# board.net
KiCad netlist of a schematic drawn in EAGLE
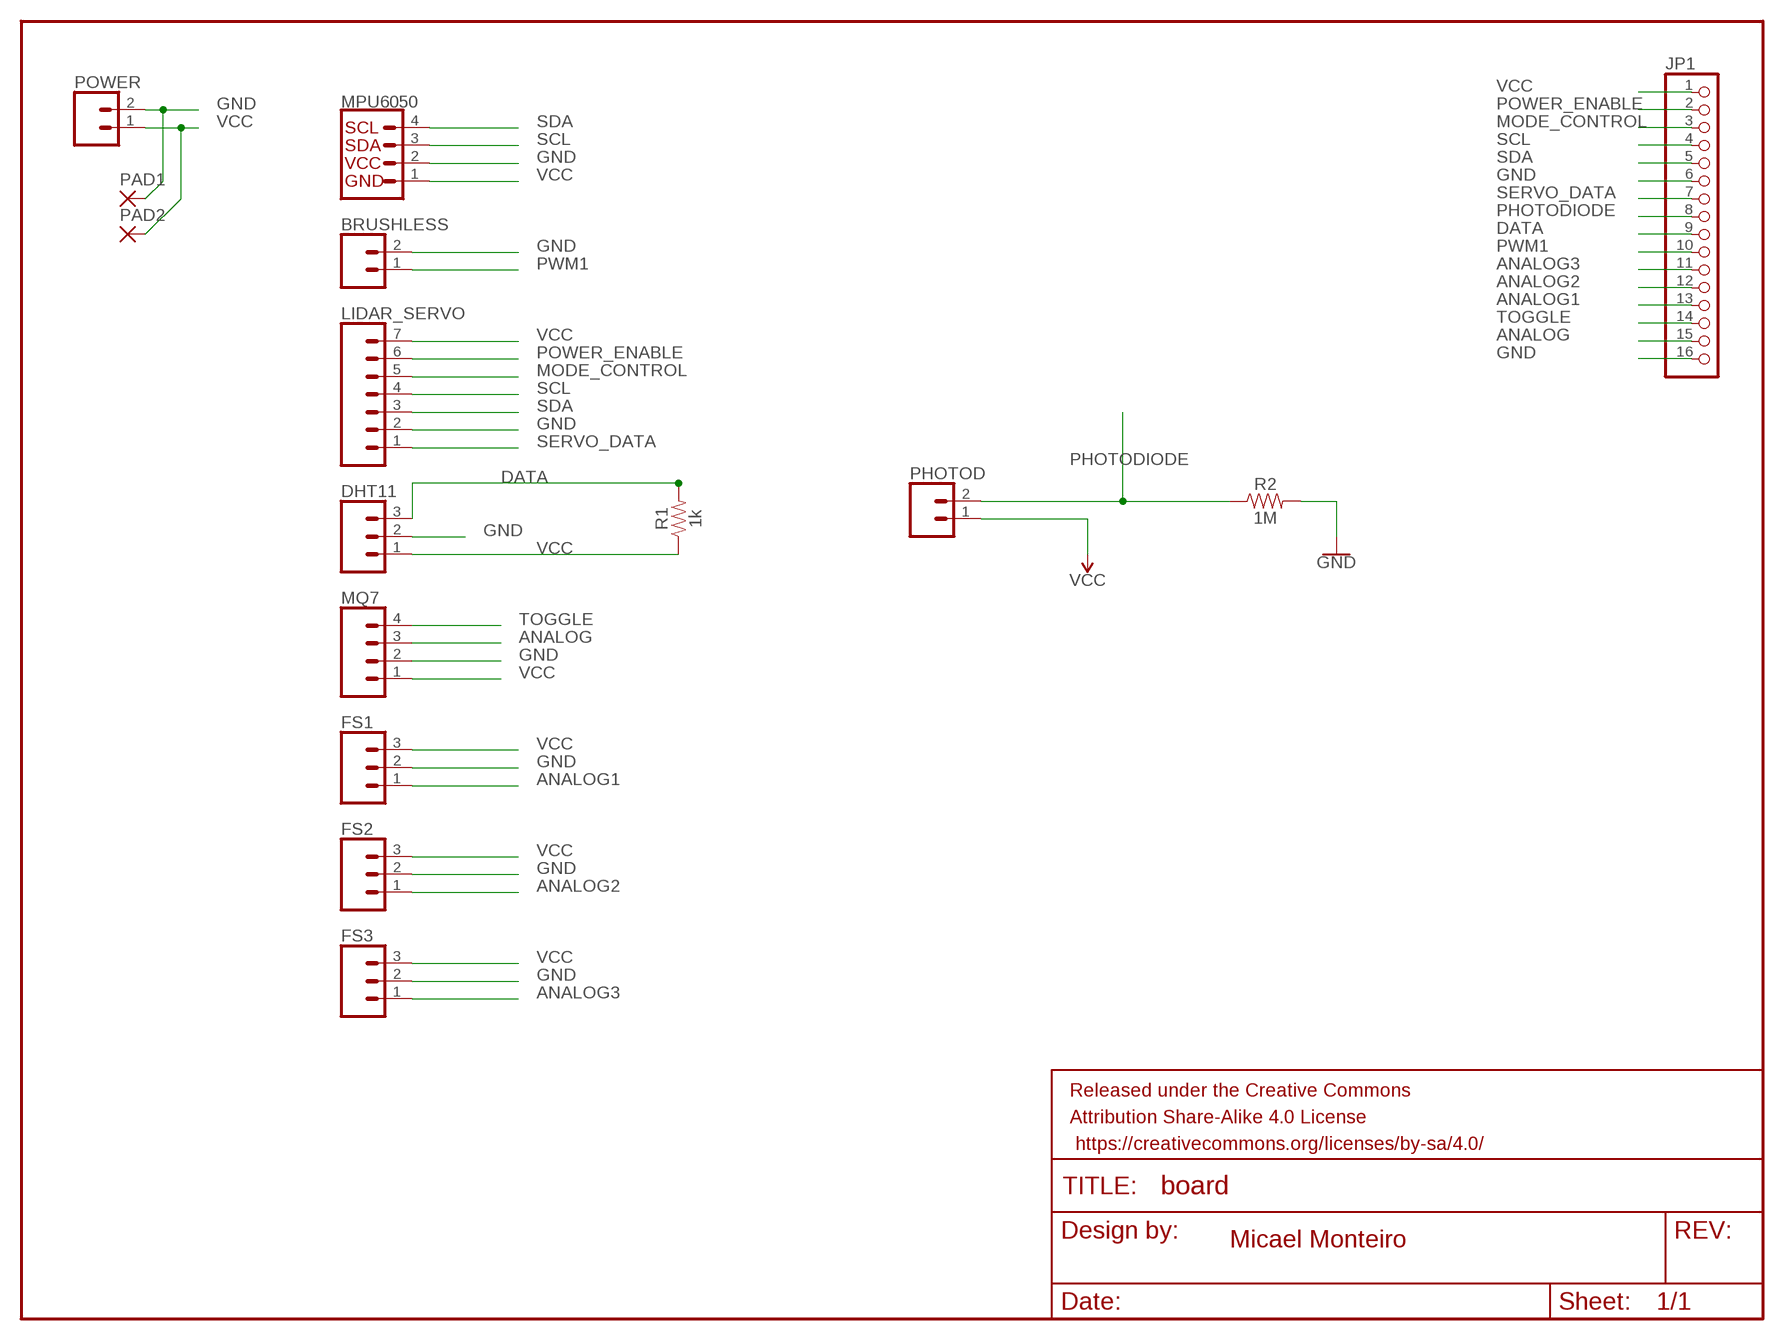
[diagram p0: schematic, sheet 1]

(export (version "E")
  (design (tool "Eeschema 10.0.6"))
  (components
    (comp (ref "BRUSHLESS")
      (value "CONN_02")
      (footprint "eagle-import:1X02")
      (libsource (lib "eagle-import") (part "CONN_02"))
    )
    (comp (ref "DHT11")
      (value "CONN_03")
      (footprint "eagle-import:1X03")
      (libsource (lib "eagle-import") (part "CONN_03"))
    )
    (comp (ref "FRAME1")
      (value "FRAME-LETTER")
      (footprint "eagle-import:CREATIVE_COMMONS")
      (libsource (lib "eagle-import") (part "FRAME-LETTER"))
    )
    (comp (ref "FS1")
      (value "CONN_03")
      (footprint "eagle-import:1X03")
      (libsource (lib "eagle-import") (part "CONN_03"))
    )
    (comp (ref "FS2")
      (value "CONN_03")
      (footprint "eagle-import:1X03")
      (libsource (lib "eagle-import") (part "CONN_03"))
    )
    (comp (ref "FS3")
      (value "CONN_03")
      (footprint "eagle-import:1X03")
      (libsource (lib "eagle-import") (part "CONN_03"))
    )
    (comp (ref "JP1")
      (value "PINHD-1X16")
      (footprint "eagle-import:1X16")
      (libsource (lib "eagle-import") (part "PINHD-1X16"))
    )
    (comp (ref "LIDAR_SERVO")
      (value "CONN_07")
      (footprint "eagle-import:1X07")
      (libsource (lib "eagle-import") (part "CONN_07"))
    )
    (comp (ref "MPU6050")
      (value "I2C_STANDARD")
      (footprint "eagle-import:1X04")
      (libsource (lib "eagle-import") (part "I2C_STANDARD"))
    )
    (comp (ref "MQ7")
      (value "CONN_04")
      (footprint "eagle-import:1X04")
      (libsource (lib "eagle-import") (part "CONN_04"))
    )
    (comp (ref "PAD1")
      (value "1,6/0,9")
      (footprint "eagle-import:1,6_0,9")
      (libsource (lib "eagle-import") (part "1,6/0,9"))
    )
    (comp (ref "PAD2")
      (value "1,6/0,9")
      (footprint "eagle-import:1,6_0,9")
      (libsource (lib "eagle-import") (part "1,6/0,9"))
    )
    (comp (ref "PHOTOD")
      (value "CONN_02")
      (footprint "eagle-import:1X02")
      (libsource (lib "eagle-import") (part "CONN_02"))
    )
    (comp (ref "POWER")
      (value "CONN_02")
      (footprint "eagle-import:1X02")
      (libsource (lib "eagle-import") (part "CONN_02"))
    )
    (comp (ref "R1")
      (value "1k")
      (footprint "eagle-import:0603")
      (libsource (lib "eagle-import") (part "1KOHM-0603-1/10W-1%"))
    )
    (comp (ref "R2")
      (value "1M")
      (footprint "eagle-import:0603")
      (libsource (lib "eagle-import") (part "1MOHM-0603-1/4W-5%"))
    )
  )
  (nets
    (net (code "1") (name "/ANALOG") (class "Default")
      (node (ref "JP1") (pin "15") (pinfunction "15_15") (pintype "passive"))
      (node (ref "MQ7") (pin "3") (pinfunction "3_3") (pintype "passive"))
    )
    (net (code "2") (name "/ANALOG1") (class "Default")
      (node (ref "FS1") (pin "1") (pinfunction "1_1") (pintype "passive"))
      (node (ref "JP1") (pin "13") (pinfunction "13_13") (pintype "passive"))
    )
    (net (code "3") (name "/ANALOG2") (class "Default")
      (node (ref "FS2") (pin "1") (pinfunction "1_1") (pintype "passive"))
      (node (ref "JP1") (pin "12") (pinfunction "12_12") (pintype "passive"))
    )
    (net (code "4") (name "/ANALOG3") (class "Default")
      (node (ref "FS3") (pin "1") (pinfunction "1_1") (pintype "passive"))
      (node (ref "JP1") (pin "11") (pinfunction "11_11") (pintype "passive"))
    )
    (net (code "5") (name "/DATA") (class "Default")
      (node (ref "DHT11") (pin "3") (pinfunction "3_3") (pintype "passive"))
      (node (ref "JP1") (pin "9") (pinfunction "9_9") (pintype "passive"))
      (node (ref "R1") (pin "2") (pinfunction "2_2") (pintype "passive"))
    )
    (net (code "6") (name "/MODE_CONTROL") (class "Default")
      (node (ref "JP1") (pin "3") (pinfunction "3_3") (pintype "passive"))
      (node (ref "LIDAR_SERVO") (pin "5") (pinfunction "5_5") (pintype "passive"))
    )
    (net (code "7") (name "/PHOTODIODE") (class "Default")
      (node (ref "JP1") (pin "8") (pinfunction "8_8") (pintype "passive"))
      (node (ref "PHOTOD") (pin "2") (pinfunction "2_2") (pintype "passive"))
      (node (ref "R2") (pin "1") (pinfunction "1_1") (pintype "passive"))
    )
    (net (code "8") (name "/POWER_ENABLE") (class "Default")
      (node (ref "JP1") (pin "2") (pinfunction "2_2") (pintype "passive"))
      (node (ref "LIDAR_SERVO") (pin "6") (pinfunction "6_6") (pintype "passive"))
    )
    (net (code "9") (name "/PWM1") (class "Default")
      (node (ref "BRUSHLESS") (pin "1") (pinfunction "1_1") (pintype "passive"))
      (node (ref "JP1") (pin "10") (pinfunction "10_10") (pintype "passive"))
    )
    (net (code "10") (name "/SCL") (class "Default")
      (node (ref "JP1") (pin "4") (pinfunction "4_4") (pintype "passive"))
      (node (ref "LIDAR_SERVO") (pin "4") (pinfunction "4_4") (pintype "passive"))
      (node (ref "MPU6050") (pin "3") (pinfunction "3_3") (pintype "passive"))
    )
    (net (code "11") (name "/SDA") (class "Default")
      (node (ref "JP1") (pin "5") (pinfunction "5_5") (pintype "passive"))
      (node (ref "LIDAR_SERVO") (pin "3") (pinfunction "3_3") (pintype "passive"))
      (node (ref "MPU6050") (pin "4") (pinfunction "4_4") (pintype "passive"))
    )
    (net (code "12") (name "/SERVO_DATA") (class "Default")
      (node (ref "JP1") (pin "7") (pinfunction "7_7") (pintype "passive"))
      (node (ref "LIDAR_SERVO") (pin "1") (pinfunction "1_1") (pintype "passive"))
    )
    (net (code "13") (name "/TOGGLE") (class "Default")
      (node (ref "JP1") (pin "14") (pinfunction "14_14") (pintype "passive"))
      (node (ref "MQ7") (pin "4") (pinfunction "4_4") (pintype "passive"))
    )
    (net (code "14") (name "GND") (class "Default")
      (node (ref "BRUSHLESS") (pin "2") (pinfunction "2_2") (pintype "passive"))
      (node (ref "DHT11") (pin "2") (pinfunction "2_2") (pintype "passive"))
      (node (ref "FS1") (pin "2") (pinfunction "2_2") (pintype "passive"))
      (node (ref "FS2") (pin "2") (pinfunction "2_2") (pintype "passive"))
      (node (ref "FS3") (pin "2") (pinfunction "2_2") (pintype "passive"))
      (node (ref "JP1") (pin "16") (pinfunction "16_16") (pintype "passive"))
      (node (ref "JP1") (pin "6") (pinfunction "6_6") (pintype "passive"))
      (node (ref "LIDAR_SERVO") (pin "2") (pinfunction "2_2") (pintype "passive"))
      (node (ref "MPU6050") (pin "2") (pinfunction "2_2") (pintype "power_in"))
      (node (ref "MQ7") (pin "2") (pinfunction "2_2") (pintype "passive"))
      (node (ref "PAD1") (pin "1") (pinfunction "P_1") (pintype "passive"))
      (node (ref "POWER") (pin "2") (pinfunction "2_2") (pintype "passive"))
      (node (ref "R2") (pin "2") (pinfunction "2_2") (pintype "passive"))
    )
    (net (code "15") (name "VCC") (class "Default")
      (node (ref "DHT11") (pin "1") (pinfunction "1_1") (pintype "passive"))
      (node (ref "FS1") (pin "3") (pinfunction "3_3") (pintype "passive"))
      (node (ref "FS2") (pin "3") (pinfunction "3_3") (pintype "passive"))
      (node (ref "FS3") (pin "3") (pinfunction "3_3") (pintype "passive"))
      (node (ref "JP1") (pin "1") (pinfunction "1_1") (pintype "passive"))
      (node (ref "LIDAR_SERVO") (pin "7") (pinfunction "7_7") (pintype "passive"))
      (node (ref "MPU6050") (pin "1") (pinfunction "1_1") (pintype "power_in"))
      (node (ref "MQ7") (pin "1") (pinfunction "1_1") (pintype "passive"))
      (node (ref "PAD2") (pin "1") (pinfunction "P_1") (pintype "passive"))
      (node (ref "PHOTOD") (pin "1") (pinfunction "1_1") (pintype "passive"))
      (node (ref "POWER") (pin "1") (pinfunction "1_1") (pintype "passive"))
      (node (ref "R1") (pin "1") (pinfunction "1_1") (pintype "passive"))
    )
  )
)
